# sheet2.net
KiCad netlist of a schematic drawn in Altium Designer
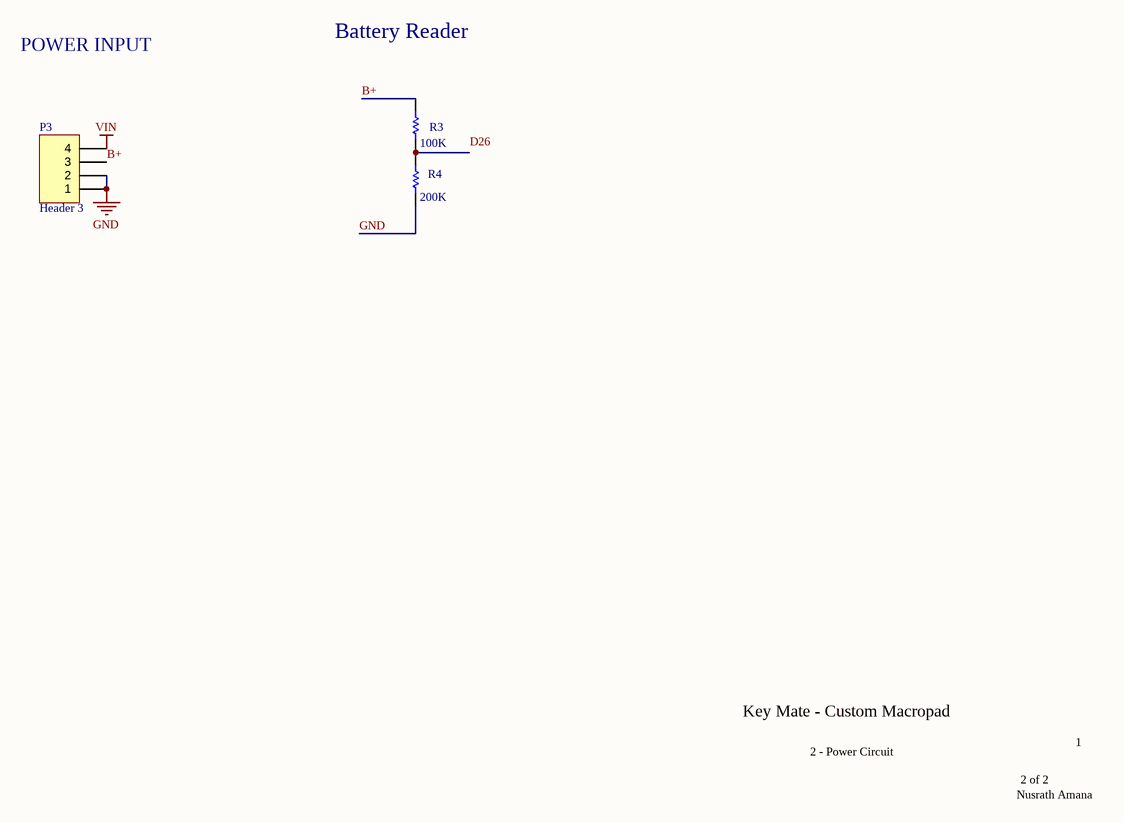
[diagram p0: sheet2.SchDoc]

(export (version "E")
  (design (tool "Eeschema 10.0.6"))
  (components
    (comp (ref "P3")
      (value "Header 3")
      (footprint "HDR1X4")
      (description "Header, 4-Pin")
      (fields (field (name "PUBLISHER") "Altium Limited"))
      (libsource (lib "Miscellaneous Connectors") (part "Header 4"))
    )
    (comp (ref "R3")
      (value "100K")
      (footprint "AXIAL-0.3")
      (description "Resistor")
      (fields (field (name "Comment") "Res1") (field (name "PUBLISHER") "Altium Limited"))
      (libsource (lib "Miscellaneous Devices") (part "Res1"))
    )
    (comp (ref "R4")
      (value "200K")
      (footprint "AXIAL-0.3")
      (description "Resistor")
      (fields (field (name "Comment") "Res1") (field (name "PUBLISHER") "Altium Limited"))
      (libsource (lib "Miscellaneous Devices") (part "Res1"))
    )
  )
  (nets
    (net (code "1") (name "/B+") (class "Default")
      (node (ref "P3") (pin "3") (pinfunction "3_3") (pintype "passive"))
      (node (ref "R3") (pin "2") (pinfunction "2_2") (pintype "passive"))
    )
    (net (code "3") (name "GND") (class "Default")
      (node (ref "P3") (pin "1") (pinfunction "1_1") (pintype "passive"))
      (node (ref "P3") (pin "2") (pinfunction "2_2") (pintype "passive"))
      (node (ref "R4") (pin "1") (pinfunction "1_1") (pintype "passive"))
    )
    (net (code "4") (name "Net-(R3-Pad1)") (class "Default")
      (node (ref "R3") (pin "1") (pinfunction "1_1") (pintype "passive"))
      (node (ref "R4") (pin "2") (pinfunction "2_2") (pintype "passive"))
    )
    (net (code "5") (name "VIN") (class "Default")
      (node (ref "P3") (pin "4") (pinfunction "4_4") (pintype "passive"))
    )
  )
)
